# led_driver.net
KiCad netlist of a schematic drawn in EAGLE
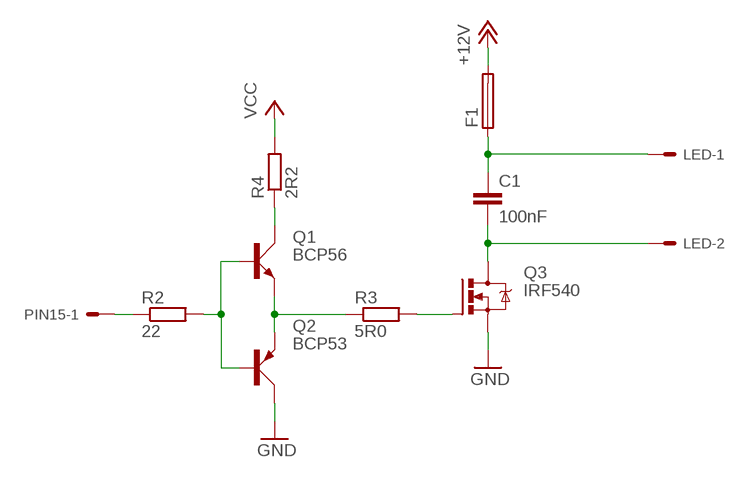
[diagram p0: schematic, sheet 1]

(export (version "E")
  (design (tool "Eeschema 10.0.6"))
  (components
    (comp (ref "C1")
      (value "100nF")
      (footprint "eagle-import:C2.5-3")
      (libsource (lib "eagle-import") (part "C2,5-3"))
    )
    (comp (ref "F1")
      (value "TE5")
      (footprint "eagle-import:TE5")
      (libsource (lib "eagle-import") (part "TE5"))
    )
    (comp (ref "LED")
      (value "5566-10")
      (footprint "eagle-import:5566-10")
      (libsource (lib "eagle-import") (part "5566-10"))
    )
    (comp (ref "PIN15")
      (value "5566-10")
      (footprint "eagle-import:5566-10")
      (libsource (lib "eagle-import") (part "5566-10"))
    )
    (comp (ref "Q1")
      (value "BCP56")
      (footprint "eagle-import:SOT54D")
      (libsource (lib "eagle-import") (part "BC639"))
    )
    (comp (ref "Q2")
      (value "BCP53")
      (footprint "eagle-import:SOT54D")
      (libsource (lib "eagle-import") (part "BC640"))
    )
    (comp (ref "Q3")
      (value "IRF540")
      (footprint "eagle-import:TO220BV")
      (libsource (lib "eagle-import") (part "IRF540"))
    )
    (comp (ref "R2")
      (value "22")
      (footprint "eagle-import:R1206")
      (libsource (lib "eagle-import") (part "R-EU_R1206"))
    )
    (comp (ref "R3")
      (value "5R0")
      (footprint "eagle-import:R1206")
      (libsource (lib "eagle-import") (part "R-EU_R1206"))
    )
    (comp (ref "R4")
      (value "2R2")
      (footprint "eagle-import:R1206")
      (libsource (lib "eagle-import") (part "R-EU_R1206"))
    )
  )
  (nets
    (net (code "1") (name "+12V") (class "Default")
      (node (ref "F1") (pin "2") (pinfunction "2_2") (pintype "passive"))
    )
    (net (code "2") (name "GND") (class "Default")
      (node (ref "Q2") (pin "C") (pinfunction "C_C") (pintype "passive"))
      (node (ref "Q3") (pin "S") (pinfunction "S_S") (pintype "passive"))
    )
    (net (code "3") (name "Net-(LEDA-S)") (class "Default")
      (node (ref "C1") (pin "1") (pinfunction "1_1") (pintype "passive"))
      (node (ref "F1") (pin "1") (pinfunction "1_1") (pintype "passive"))
      (node (ref "LED") (pin "1") (pinfunction "S_1") (pintype "passive"))
    )
    (net (code "4") (name "Net-(LEDC-S)") (class "Default")
      (node (ref "C1") (pin "2") (pinfunction "2_2") (pintype "passive"))
      (node (ref "LED") (pin "2") (pinfunction "S_2") (pintype "passive"))
      (node (ref "Q3") (pin "D") (pinfunction "D_D") (pintype "passive"))
    )
    (net (code "5") (name "Net-(PIN15A-S)") (class "Default")
      (node (ref "PIN15") (pin "1") (pinfunction "S_1") (pintype "passive"))
      (node (ref "R2") (pin "1") (pinfunction "1_1") (pintype "passive"))
    )
    (net (code "6") (name "Net-(Q1-PadB)") (class "Default")
      (node (ref "Q1") (pin "B") (pinfunction "B_B") (pintype "passive"))
      (node (ref "Q2") (pin "B") (pinfunction "B_B") (pintype "passive"))
      (node (ref "R2") (pin "2") (pinfunction "2_2") (pintype "passive"))
    )
    (net (code "7") (name "Net-(Q1-PadC)") (class "Default")
      (node (ref "Q1") (pin "C") (pinfunction "C_C") (pintype "passive"))
      (node (ref "R4") (pin "1") (pinfunction "1_1") (pintype "passive"))
    )
    (net (code "8") (name "Net-(Q1-PadE)") (class "Default")
      (node (ref "Q1") (pin "E") (pinfunction "E_E") (pintype "passive"))
      (node (ref "Q2") (pin "E") (pinfunction "E_E") (pintype "passive"))
      (node (ref "R3") (pin "1") (pinfunction "1_1") (pintype "passive"))
    )
    (net (code "9") (name "Net-(Q3-PadG)") (class "Default")
      (node (ref "Q3") (pin "G") (pinfunction "G_G") (pintype "passive"))
      (node (ref "R3") (pin "2") (pinfunction "2_2") (pintype "passive"))
    )
    (net (code "10") (name "VCC") (class "Default")
      (node (ref "R4") (pin "2") (pinfunction "2_2") (pintype "passive"))
    )
  )
)
